# ARM_EURO_Platine1.net
KiCad netlist of a schematic drawn in Altium Designer
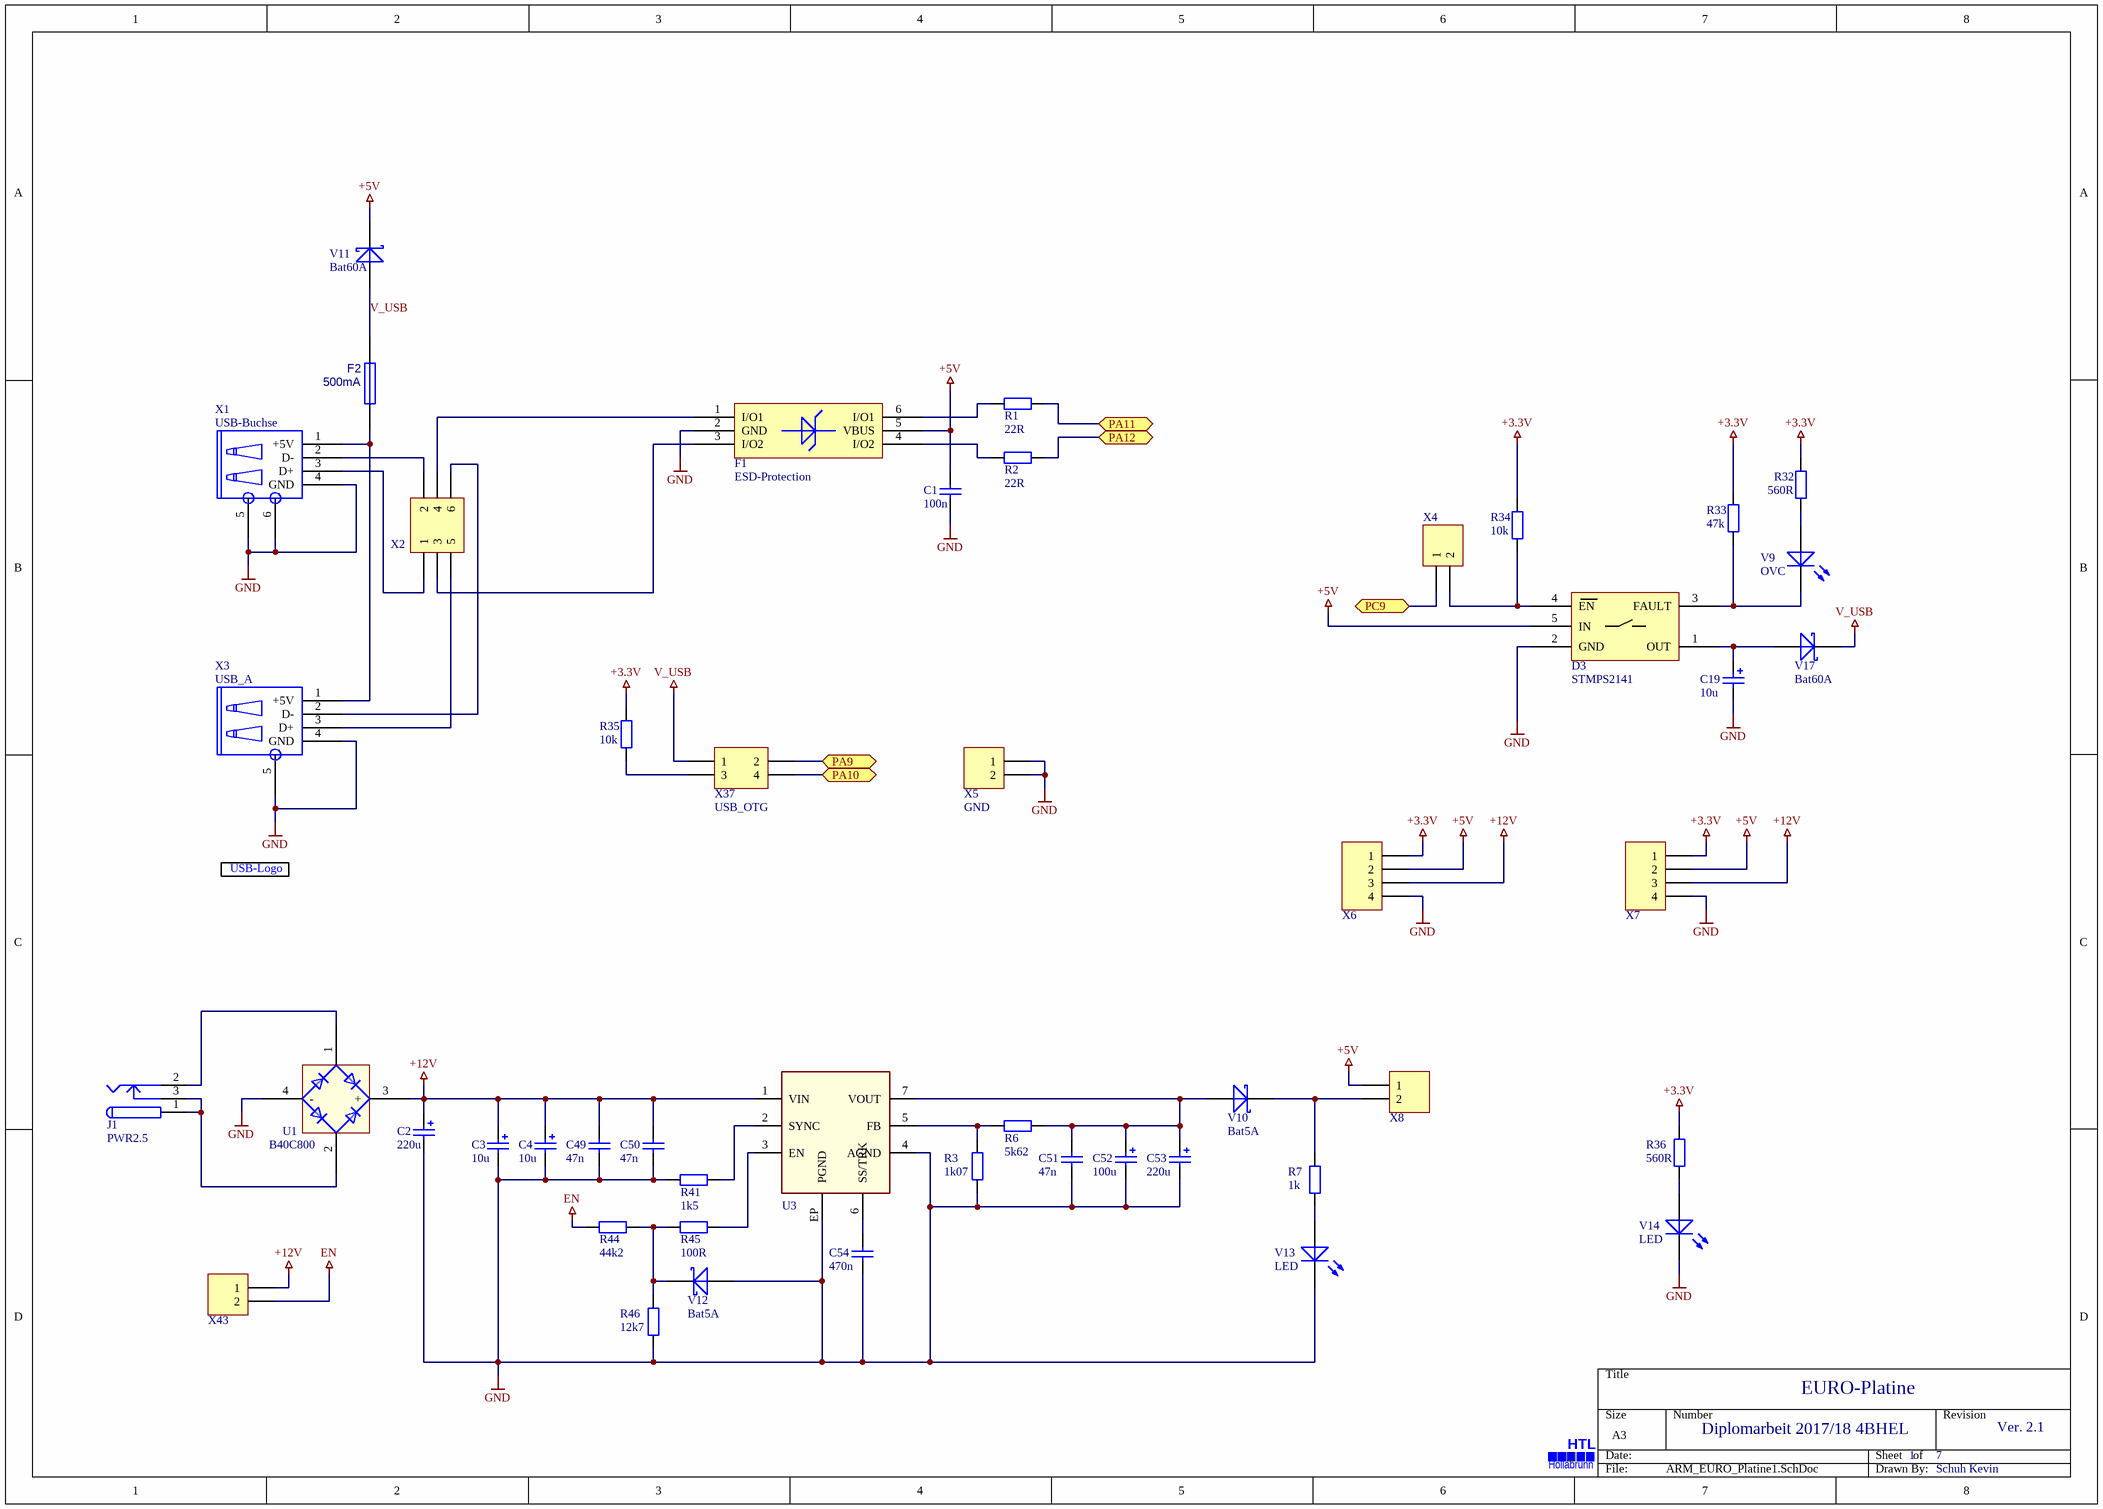
[diagram p0: ARM_EURO_Platine1.SchDoc]

(export (version "E")
  (design (tool "Eeschema 10.0.6"))
  (components
    (comp (ref "*1")
      (value "USB_Logo")
      (footprint "USB_Logo")
      (description "Logo")
      (libsource (lib "ARM_Libary_EURO") (part "USB_Logo"))
    )
    (comp (ref "A1")
      (value "HTL Hollabrunn")
      (footprint "HTL_Logo")
      (libsource (lib "ARM_Libary_EURO") (part "HTL_Logo"))
    )
    (comp (ref "C1")
      (value "100n")
      (footprint "0805_CAP")
      (description "Capacitor_SMD")
      (fields (field (name "Comment") "Cap_Keramik_SMD") (field (name "PUBLISHER") "Altium Limited"))
      (libsource (lib "ARM_Libary_EURO") (part "Cap_Keramik_SMD"))
    )
    (comp (ref "C2")
      (value "220u")
      (footprint "100µF_16V_Kondensator")
      (description "Polarized Capacitor SMD")
      (fields (field (name "Comment") "Cap_Pol_SMD") (field (name "PUBLISHER") "Altium Limited"))
      (libsource (lib "ARM_Libary_EURO") (part "Cap_Pol_SMD"))
    )
    (comp (ref "C3")
      (value "10u")
      (footprint "1411_Cap_Pol_Tantal")
      (description "Polarized Capacitor")
      (fields (field (name "Comment") "Cap_Pol_Tantal") (field (name "PUBLISHER") "Altium Limited"))
      (libsource (lib "ARM_Libary_EURO") (part "Cap_Pol_Tantal"))
    )
    (comp (ref "C4")
      (value "10u")
      (footprint "1411_Cap_Pol_Tantal")
      (description "Polarized Capacitor")
      (fields (field (name "Comment") "Cap_Pol_Tantal") (field (name "PUBLISHER") "Altium Limited"))
      (libsource (lib "ARM_Libary_EURO") (part "Cap_Pol_Tantal"))
    )
    (comp (ref "C19")
      (value "10u")
      (footprint "100µF_16V_Kondensator")
      (description "Polarized Capacitor SMD")
      (fields (field (name "Comment") "Cap_Pol_SMD") (field (name "PUBLISHER") "Altium Limited"))
      (libsource (lib "ARM_Libary_EURO") (part "Cap_Pol_SMD"))
    )
    (comp (ref "C49")
      (value "47n")
      (footprint "0805_CAP")
      (description "Capacitor_SMD")
      (fields (field (name "Comment") "Cap_Keramik_SMD") (field (name "PUBLISHER") "Altium Limited"))
      (libsource (lib "ARM_Libary_EURO") (part "Cap_Keramik_SMD"))
    )
    (comp (ref "C50")
      (value "47n")
      (footprint "0805_CAP")
      (description "Capacitor_SMD")
      (fields (field (name "Comment") "Cap_Keramik_SMD") (field (name "PUBLISHER") "Altium Limited"))
      (libsource (lib "ARM_Libary_EURO") (part "Cap_Keramik_SMD"))
    )
    (comp (ref "C51")
      (value "47n")
      (footprint "0805_CAP")
      (description "Capacitor_SMD")
      (fields (field (name "Comment") "Cap_Keramik_SMD") (field (name "PUBLISHER") "Altium Limited"))
      (libsource (lib "ARM_Libary_EURO") (part "Cap_Keramik_SMD"))
    )
    (comp (ref "C52")
      (value "100u")
      (footprint "100µF_16V_Kondensator")
      (description "Polarized Capacitor SMD")
      (fields (field (name "Comment") "Cap_Pol_SMD") (field (name "PUBLISHER") "Altium Limited"))
      (libsource (lib "ARM_Libary_EURO") (part "Cap_Pol_SMD"))
    )
    (comp (ref "C53")
      (value "220u")
      (footprint "100µF_16V_Kondensator")
      (description "Polarized Capacitor SMD")
      (fields (field (name "Comment") "Cap_Pol_SMD") (field (name "PUBLISHER") "Altium Limited"))
      (libsource (lib "ARM_Libary_EURO") (part "Cap_Pol_SMD"))
    )
    (comp (ref "C54")
      (value "470n")
      (footprint "0805_CAP")
      (description "Capacitor_SMD")
      (fields (field (name "Comment") "Cap_Keramik_SMD") (field (name "PUBLISHER") "Altium Limited"))
      (libsource (lib "ARM_Libary_EURO") (part "Cap_Keramik_SMD"))
    )
    (comp (ref "D3")
      (value "STMPS2141")
      (footprint "STMPS2141")
      (description "Power Switch")
      (libsource (lib "ARM_Libary_EURO") (part "STMPS2141"))
    )
    (comp (ref "F1")
      (value "ESD-Protection")
      (footprint "USBLC6_2")
      (description "Schutz vor entladungen über USB-Buchse")
      (libsource (lib "ARM_Libary_EURO") (part "USBLC6_2"))
    )
    (comp (ref "F2")
      (value "500mA")
      (footprint "Polyfuse")
      (description "Fuse")
      (fields (field (name "PUBLISHER") "Altium Limited"))
      (libsource (lib "ARM_Libary_EURO") (part "Fuse"))
    )
    (comp (ref "J1")
      (value "PWR2.5")
      (footprint "PowerJack")
      (description "Low Voltage Power Supply Connector")
      (fields (field (name "PUBLISHER") "Altium Limited"))
      (libsource (lib "ARM_Libary_EURO") (part "PWR2.5"))
    )
    (comp (ref "R1")
      (value "22R")
      (footprint "0805_Res")
      (description "Resistor")
      (fields (field (name "Comment") "Res_SMD") (field (name "PUBLISHER") "Altium Limited"))
      (libsource (lib "") (part "Res_SMD_2"))
    )
    (comp (ref "R2")
      (value "22R")
      (footprint "0805_Res")
      (description "Resistor")
      (fields (field (name "Comment") "Res_SMD") (field (name "PUBLISHER") "Altium Limited"))
      (libsource (lib "") (part "Res_SMD_2"))
    )
    (comp (ref "R3")
      (value "1k07")
      (footprint "0805_Res")
      (description "Resistor")
      (fields (field (name "Comment") "Res_SMD") (field (name "PUBLISHER") "Altium Limited"))
      (libsource (lib "") (part "Res_SMD_1"))
    )
    (comp (ref "R6")
      (value "5k62")
      (footprint "0805_Res")
      (description "Resistor")
      (fields (field (name "Comment") "Res_SMD") (field (name "PUBLISHER") "Altium Limited"))
      (libsource (lib "ARM_Libary_EURO") (part "Res_SMD"))
    )
    (comp (ref "R7")
      (value "1k")
      (footprint "0805_Res")
      (description "Resistor")
      (fields (field (name "Comment") "Res_SMD") (field (name "PUBLISHER") "Altium Limited"))
      (libsource (lib "") (part "Res_SMD_1"))
    )
    (comp (ref "R32")
      (value "560R")
      (footprint "0805_Res")
      (description "Resistor")
      (fields (field (name "Comment") "Res_SMD") (field (name "PUBLISHER") "Altium Limited"))
      (libsource (lib "") (part "Res_SMD_1"))
    )
    (comp (ref "R33")
      (value "47k")
      (footprint "0805_Res")
      (description "Resistor")
      (fields (field (name "Comment") "Res_SMD") (field (name "PUBLISHER") "Altium Limited"))
      (libsource (lib "") (part "Res_SMD_1"))
    )
    (comp (ref "R34")
      (value "10k")
      (footprint "0805_Res")
      (description "Resistor")
      (fields (field (name "Comment") "Res_SMD") (field (name "PUBLISHER") "Altium Limited"))
      (libsource (lib "") (part "Res_SMD_1"))
    )
    (comp (ref "R35")
      (value "10k")
      (footprint "0805_Res")
      (description "Resistor")
      (fields (field (name "Comment") "Res_SMD") (field (name "PUBLISHER") "Altium Limited"))
      (libsource (lib "") (part "Res_SMD_1"))
    )
    (comp (ref "R36")
      (value "560R")
      (footprint "0805_Res")
      (description "Resistor")
      (fields (field (name "Comment") "Res_SMD") (field (name "PUBLISHER") "Altium Limited"))
      (libsource (lib "") (part "Res_SMD_1"))
    )
    (comp (ref "R41")
      (value "1k5")
      (footprint "0805_Res")
      (description "Resistor")
      (fields (field (name "Comment") "Res_SMD") (field (name "PUBLISHER") "Altium Limited"))
      (libsource (lib "ARM_Libary_EURO") (part "Res_SMD"))
    )
    (comp (ref "R44")
      (value "44k2")
      (footprint "0805_Res")
      (description "Resistor")
      (fields (field (name "Comment") "Res_SMD") (field (name "PUBLISHER") "Altium Limited"))
      (libsource (lib "ARM_Libary_EURO") (part "Res_SMD"))
    )
    (comp (ref "R45")
      (value "100R")
      (footprint "0805_Res")
      (description "Resistor")
      (fields (field (name "Comment") "Res_SMD") (field (name "PUBLISHER") "Altium Limited"))
      (libsource (lib "ARM_Libary_EURO") (part "Res_SMD"))
    )
    (comp (ref "R46")
      (value "12k7")
      (footprint "0805_Res")
      (description "Resistor")
      (fields (field (name "Comment") "Res_SMD") (field (name "PUBLISHER") "Altium Limited"))
      (libsource (lib "") (part "Res_SMD_1"))
    )
    (comp (ref "U1")
      (value "B40C800")
      (footprint "Diodengleichrichter")
      (description "Brueckengleichrichter")
      (libsource (lib "ARM_Libary_EURO") (part "Brueckengleichrichter"))
    )
    (comp (ref "U3")
      (value "171050601")
      (footprint "TO263-7EP")
      (description "VDRM Variable Step Down Regulator Module, TO263-7EP")
      (fields (field (name "PUBLISHER") "Wurth Elektronik"))
      (libsource (lib "ARM_Libary_EURO") (part "171050601"))
    )
    (comp (ref "V9")
      (value "OVC")
      (footprint "0805_LED")
      (description "Typical RED, GREEN, YELLOW, AMBER GaAs LED")
      (fields (field (name "PUBLISHER") "Altium Limited"))
      (libsource (lib "ARM_Libary_EURO") (part "LED_SMD"))
    )
    (comp (ref "V10")
      (value "Bat5A")
      (footprint "BAT254_Schottky")
      (description "Diode")
      (libsource (lib "ARM_Libary_EURO") (part "Bat60A"))
    )
    (comp (ref "V11")
      (value "Bat60A")
      (footprint "BAT254_Schottky")
      (description "Diode")
      (libsource (lib "ARM_Libary_EURO") (part "Bat60A"))
    )
    (comp (ref "V12")
      (value "Bat5A")
      (footprint "BAT254_Schottky")
      (description "Diode")
      (libsource (lib "ARM_Libary_EURO") (part "Bat60A"))
    )
    (comp (ref "V13")
      (value "LED")
      (footprint "0805_LED")
      (description "Typical RED, GREEN, YELLOW, AMBER GaAs LED")
      (fields (field (name "PUBLISHER") "Altium Limited"))
      (libsource (lib "ARM_Libary_EURO") (part "LED_SMD"))
    )
    (comp (ref "V14")
      (value "LED")
      (footprint "0805_LED")
      (description "Typical RED, GREEN, YELLOW, AMBER GaAs LED")
      (fields (field (name "PUBLISHER") "Altium Limited"))
      (libsource (lib "ARM_Libary_EURO") (part "LED_SMD"))
    )
    (comp (ref "V17")
      (value "Bat60A")
      (footprint "BAT254_Schottky")
      (description "Diode")
      (libsource (lib "ARM_Libary_EURO") (part "Bat60A"))
    )
    (comp (ref "X1")
      (value "USB-Buchse")
      (footprint "USB_B")
      (description "USB Buchse (B)")
      (libsource (lib "ARM_Libary_EURO") (part "USB_Buchse_B"))
    )
    (comp (ref "X2")
      (value "Header_3x2")
      (footprint "HDR2X3")
      (description "Header, 3x2-Pin")
      (fields (field (name "PUBLISHER") "Altium Limited"))
      (libsource (lib "ARM_Libary_EURO") (part "Header_3x2"))
    )
    (comp (ref "X3")
      (value "USB_A")
      (footprint "USB_A")
      (description "USB Buchse (A)")
      (libsource (lib "ARM_Libary_EURO") (part "USB_Buchse_A"))
    )
    (comp (ref "X4")
      (value "Header")
      (footprint "HDR1X2")
      (description "Header, 2-Pin")
      (fields (field (name "PUBLISHER") "Altium Limited"))
      (libsource (lib "ARM_Libary_EURO") (part "Header_2"))
    )
    (comp (ref "X5")
      (value "GND")
      (footprint "HDR1X2")
      (description "Header, 2-Pin")
      (fields (field (name "PUBLISHER") "Altium Limited"))
      (libsource (lib "ARM_Libary_EURO") (part "Masseschleife"))
    )
    (comp (ref "X6")
      (value "Header_4")
      (footprint "HDR1X4")
      (description "Header, 3-Pin")
      (fields (field (name "PUBLISHER") "Altium Limited"))
      (libsource (lib "ARM_Libary_EURO") (part "Header_4"))
    )
    (comp (ref "X7")
      (value "Header_4")
      (footprint "HDR1X4")
      (description "Header, 3-Pin")
      (fields (field (name "PUBLISHER") "Altium Limited"))
      (libsource (lib "ARM_Libary_EURO") (part "Header_4"))
    )
    (comp (ref "X8")
      (value "Header")
      (footprint "HDR1X2")
      (description "Header, 2-Pin")
      (fields (field (name "PUBLISHER") "Altium Limited"))
      (libsource (lib "") (part "Header_2_2"))
    )
    (comp (ref "X37")
      (value "USB_OTG")
      (footprint "HDR2X2")
      (description "Header, 3x2-Pin")
      (fields (field (name "PUBLISHER") "Altium Limited"))
      (libsource (lib "ARM_Libary_EURO") (part "Header_2x2"))
    )
    (comp (ref "X43")
      (value "Header")
      (footprint "HDR1X2")
      (description "Header, 2-Pin")
      (fields (field (name "PUBLISHER") "Altium Limited"))
      (libsource (lib "") (part "Header_2_1"))
    )
  )
  (nets
    (net (code "1") (name "+3.3V") (class "Default")
      (node (ref "R32") (pin "2") (pinfunction "2_2") (pintype "passive"))
      (node (ref "R33") (pin "2") (pinfunction "2_2") (pintype "passive"))
      (node (ref "R34") (pin "2") (pinfunction "2_2") (pintype "passive"))
      (node (ref "R35") (pin "2") (pinfunction "2_2") (pintype "passive"))
      (node (ref "R36") (pin "2") (pinfunction "2_2") (pintype "passive"))
      (node (ref "X6") (pin "1") (pinfunction "1_1") (pintype "passive"))
      (node (ref "X7") (pin "1") (pinfunction "1_1") (pintype "passive"))
    )
    (net (code "2") (name "+5V") (class "Default")
      (node (ref "C1") (pin "2") (pinfunction "2_2") (pintype "passive"))
      (node (ref "D3") (pin "5") (pinfunction "IN_5") (pintype "passive"))
      (node (ref "F1") (pin "5") (pinfunction "VBUS_5") (pintype "passive"))
      (node (ref "V11") (pin "1") (pinfunction "1_1") (pintype "passive"))
      (node (ref "X6") (pin "2") (pinfunction "2_2") (pintype "passive"))
      (node (ref "X7") (pin "2") (pinfunction "2_2") (pintype "passive"))
      (node (ref "X8") (pin "1") (pinfunction "1_1") (pintype "passive"))
    )
    (net (code "3") (name "+12V") (class "Default")
      (node (ref "C2") (pin "1") (pinfunction "1_1") (pintype "passive"))
      (node (ref "C3") (pin "1") (pinfunction "1_1") (pintype "passive"))
      (node (ref "C4") (pin "1") (pinfunction "1_1") (pintype "passive"))
      (node (ref "C49") (pin "2") (pinfunction "2_2") (pintype "passive"))
      (node (ref "C50") (pin "1") (pinfunction "1_1") (pintype "passive"))
      (node (ref "U1") (pin "3") (pinfunction "+_3") (pintype "passive"))
      (node (ref "U3") (pin "1") (pinfunction "VIN_1") (pintype "passive"))
      (node (ref "X43") (pin "1") (pinfunction "1_1") (pintype "passive"))
      (node (ref "X6") (pin "3") (pinfunction "3_3") (pintype "passive"))
      (node (ref "X7") (pin "3") (pinfunction "3_3") (pintype "passive"))
    )
    (net (code "4") (name "/PA9") (class "Default")
      (node (ref "X37") (pin "2") (pinfunction "2_2") (pintype "passive"))
    )
    (net (code "5") (name "/PA10") (class "Default")
      (node (ref "X37") (pin "4") (pinfunction "4_4") (pintype "passive"))
    )
    (net (code "6") (name "/PA11") (class "Default")
      (node (ref "R1") (pin "2") (pinfunction "2_2") (pintype "passive"))
    )
    (net (code "7") (name "/PA12") (class "Default")
      (node (ref "R2") (pin "2") (pinfunction "2_2") (pintype "passive"))
    )
    (net (code "8") (name "/PC9") (class "Default")
      (node (ref "X4") (pin "1") (pinfunction "1_1") (pintype "passive"))
    )
    (net (code "9") (name "EN") (class "Default")
      (node (ref "R44") (pin "2") (pinfunction "2_2") (pintype "passive"))
      (node (ref "X43") (pin "2") (pinfunction "2_2") (pintype "passive"))
    )
    (net (code "10") (name "GND") (class "Default")
      (node (ref "C1") (pin "1") (pinfunction "1_1") (pintype "passive"))
      (node (ref "C19") (pin "2") (pinfunction "2_2") (pintype "passive"))
      (node (ref "C2") (pin "2") (pinfunction "2_2") (pintype "passive"))
      (node (ref "C3") (pin "2") (pinfunction "2_2") (pintype "passive"))
      (node (ref "C4") (pin "2") (pinfunction "2_2") (pintype "passive"))
      (node (ref "C49") (pin "1") (pinfunction "1_1") (pintype "passive"))
      (node (ref "C50") (pin "2") (pinfunction "2_2") (pintype "passive"))
      (node (ref "C51") (pin "2") (pinfunction "2_2") (pintype "passive"))
      (node (ref "C52") (pin "2") (pinfunction "2_2") (pintype "passive"))
      (node (ref "C53") (pin "2") (pinfunction "2_2") (pintype "passive"))
      (node (ref "C54") (pin "2") (pinfunction "2_2") (pintype "passive"))
      (node (ref "D3") (pin "2") (pinfunction "GND_2") (pintype "passive"))
      (node (ref "F1") (pin "2") (pinfunction "GND_2") (pintype "passive"))
      (node (ref "R3") (pin "1") (pinfunction "1_1") (pintype "passive"))
      (node (ref "R41") (pin "2") (pinfunction "2_2") (pintype "passive"))
      (node (ref "R46") (pin "1") (pinfunction "1_1") (pintype "passive"))
      (node (ref "U1") (pin "4") (pinfunction "-_4") (pintype "passive"))
      (node (ref "U3") (pin "4") (pinfunction "AGND_4") (pintype "passive"))
      (node (ref "U3") (pin "EP") (pinfunction "PGND_EP") (pintype "passive"))
      (node (ref "V12") (pin "2") (pinfunction "2_2") (pintype "passive"))
      (node (ref "V13") (pin "2") (pinfunction "K_2") (pintype "passive"))
      (node (ref "V14") (pin "2") (pinfunction "K_2") (pintype "passive"))
      (node (ref "X1") (pin "4") (pinfunction "GND_4") (pintype "passive"))
      (node (ref "X1") (pin "5") (pinfunction "GND_5") (pintype "passive"))
      (node (ref "X1") (pin "6") (pinfunction "GND_6") (pintype "passive"))
      (node (ref "X3") (pin "4") (pinfunction "GND_4") (pintype "passive"))
      (node (ref "X3") (pin "5") (pinfunction "GND_5") (pintype "passive"))
      (node (ref "X5") (pin "1") (pinfunction "1_1") (pintype "passive"))
      (node (ref "X5") (pin "2") (pinfunction "2_2") (pintype "passive"))
      (node (ref "X6") (pin "4") (pinfunction "4_4") (pintype "passive"))
      (node (ref "X7") (pin "4") (pinfunction "4_4") (pintype "passive"))
    )
    (net (code "11") (name "Net-(D3-EN)") (class "Default")
      (node (ref "D3") (pin "4") (pinfunction "EN_4") (pintype "passive"))
      (node (ref "R34") (pin "1") (pinfunction "1_1") (pintype "passive"))
      (node (ref "X4") (pin "2") (pinfunction "2_2") (pintype "passive"))
    )
    (net (code "12") (name "Net-(D3-FAULT)") (class "Default")
      (node (ref "D3") (pin "3") (pinfunction "FAULT_3") (pintype "passive"))
      (node (ref "R33") (pin "1") (pinfunction "1_1") (pintype "passive"))
      (node (ref "V9") (pin "2") (pinfunction "K_2") (pintype "passive"))
    )
    (net (code "13") (name "Net-(D3-OUT)") (class "Default")
      (node (ref "C19") (pin "1") (pinfunction "1_1") (pintype "passive"))
      (node (ref "D3") (pin "1") (pinfunction "OUT_1") (pintype "passive"))
      (node (ref "V17") (pin "2") (pinfunction "2_2") (pintype "passive"))
    )
    (net (code "14") (name "Net-(F1-I{slash}O1-Pad1)") (class "Default")
      (node (ref "F1") (pin "1") (pinfunction "I/O1_1") (pintype "passive"))
      (node (ref "X2") (pin "4") (pinfunction "4_4") (pintype "passive"))
    )
    (net (code "15") (name "Net-(F1-I{slash}O1-Pad6)") (class "Default")
      (node (ref "F1") (pin "6") (pinfunction "I/O1_6") (pintype "passive"))
      (node (ref "R1") (pin "1") (pinfunction "1_1") (pintype "passive"))
    )
    (net (code "16") (name "Net-(F1-I{slash}O2-Pad3)") (class "Default")
      (node (ref "F1") (pin "3") (pinfunction "I/O2_3") (pintype "passive"))
      (node (ref "X2") (pin "3") (pinfunction "3_3") (pintype "passive"))
    )
    (net (code "17") (name "Net-(F1-I{slash}O2-Pad4)") (class "Default")
      (node (ref "F1") (pin "4") (pinfunction "I/O2_4") (pintype "passive"))
      (node (ref "R2") (pin "1") (pinfunction "1_1") (pintype "passive"))
    )
    (net (code "18") (name "Net-(J1-Pad1)") (class "Default")
      (node (ref "J1") (pin "1") (pinfunction "1_1") (pintype "power_in"))
      (node (ref "J1") (pin "3") (pinfunction "3_3") (pintype "power_in"))
      (node (ref "U1") (pin "2") (pinfunction "2_2") (pintype "passive"))
    )
    (net (code "19") (name "Net-(J1-Pad2)") (class "Default")
      (node (ref "J1") (pin "2") (pinfunction "2_2") (pintype "power_in"))
      (node (ref "U1") (pin "1") (pinfunction "1_1") (pintype "passive"))
    )
    (net (code "20") (name "Net-(R7-Pad2)") (class "Default")
      (node (ref "R7") (pin "2") (pinfunction "2_2") (pintype "passive"))
      (node (ref "V10") (pin "1") (pinfunction "1_1") (pintype "passive"))
      (node (ref "X8") (pin "2") (pinfunction "2_2") (pintype "passive"))
    )
    (net (code "21") (name "Net-(R35-Pad1)") (class "Default")
      (node (ref "R35") (pin "1") (pinfunction "1_1") (pintype "passive"))
      (node (ref "X37") (pin "3") (pinfunction "3_3") (pintype "passive"))
    )
    (net (code "22") (name "Net-(R44-Pad1)") (class "Default")
      (node (ref "R44") (pin "1") (pinfunction "1_1") (pintype "passive"))
      (node (ref "R45") (pin "2") (pinfunction "2_2") (pintype "passive"))
      (node (ref "R46") (pin "2") (pinfunction "2_2") (pintype "passive"))
      (node (ref "V12") (pin "1") (pinfunction "1_1") (pintype "passive"))
    )
    (net (code "23") (name "Net-(U3-EN)") (class "Default")
      (node (ref "R45") (pin "1") (pinfunction "1_1") (pintype "passive"))
      (node (ref "U3") (pin "3") (pinfunction "EN_3") (pintype "passive"))
    )
    (net (code "24") (name "Net-(U3-FB)") (class "Default")
      (node (ref "R3") (pin "2") (pinfunction "2_2") (pintype "passive"))
      (node (ref "R6") (pin "2") (pinfunction "2_2") (pintype "passive"))
      (node (ref "U3") (pin "5") (pinfunction "FB_5") (pintype "passive"))
    )
    (net (code "25") (name "Net-(U3-SS{slash}TRK)") (class "Default")
      (node (ref "C54") (pin "1") (pinfunction "1_1") (pintype "passive"))
      (node (ref "U3") (pin "6") (pinfunction "SS/TRK_6") (pintype "passive"))
    )
    (net (code "26") (name "Net-(U3-SYNC)") (class "Default")
      (node (ref "R41") (pin "1") (pinfunction "1_1") (pintype "passive"))
      (node (ref "U3") (pin "2") (pinfunction "SYNC_2") (pintype "passive"))
    )
    (net (code "27") (name "Net-(U3-VOUT)") (class "Default")
      (node (ref "C51") (pin "1") (pinfunction "1_1") (pintype "passive"))
      (node (ref "C52") (pin "1") (pinfunction "1_1") (pintype "passive"))
      (node (ref "C53") (pin "1") (pinfunction "1_1") (pintype "passive"))
      (node (ref "R6") (pin "1") (pinfunction "1_1") (pintype "passive"))
      (node (ref "U3") (pin "7") (pinfunction "VOUT_7") (pintype "passive"))
      (node (ref "V10") (pin "2") (pinfunction "2_2") (pintype "passive"))
    )
    (net (code "28") (name "Net-(V9-A)") (class "Default")
      (node (ref "R32") (pin "1") (pinfunction "1_1") (pintype "passive"))
      (node (ref "V9") (pin "1") (pinfunction "A_1") (pintype "passive"))
    )
    (net (code "29") (name "Net-(V13-A)") (class "Default")
      (node (ref "R7") (pin "1") (pinfunction "1_1") (pintype "passive"))
      (node (ref "V13") (pin "1") (pinfunction "A_1") (pintype "passive"))
    )
    (net (code "30") (name "Net-(V14-A)") (class "Default")
      (node (ref "R36") (pin "1") (pinfunction "1_1") (pintype "passive"))
      (node (ref "V14") (pin "1") (pinfunction "A_1") (pintype "passive"))
    )
    (net (code "31") (name "Net-(X1-+5V)") (class "Default")
      (node (ref "F2") (pin "1") (pinfunction "1_1") (pintype "passive"))
      (node (ref "X1") (pin "1") (pinfunction "+5V_1") (pintype "passive"))
      (node (ref "X3") (pin "1") (pinfunction "+5V_1") (pintype "passive"))
    )
    (net (code "32") (name "Net-(X1-D+)") (class "Default")
      (node (ref "X1") (pin "3") (pinfunction "D+_3") (pintype "passive"))
      (node (ref "X2") (pin "1") (pinfunction "1_1") (pintype "passive"))
    )
    (net (code "33") (name "Net-(X1-D-)") (class "Default")
      (node (ref "X1") (pin "2") (pinfunction "D-_2") (pintype "passive"))
      (node (ref "X2") (pin "2") (pinfunction "2_2") (pintype "passive"))
    )
    (net (code "34") (name "Net-(X3-D+)") (class "Default")
      (node (ref "X2") (pin "5") (pinfunction "5_5") (pintype "passive"))
      (node (ref "X3") (pin "3") (pinfunction "D+_3") (pintype "passive"))
    )
    (net (code "35") (name "Net-(X3-D-)") (class "Default")
      (node (ref "X2") (pin "6") (pinfunction "6_6") (pintype "passive"))
      (node (ref "X3") (pin "2") (pinfunction "D-_2") (pintype "passive"))
    )
    (net (code "36") (name "V_USB") (class "Default")
      (node (ref "F2") (pin "2") (pinfunction "2_2") (pintype "passive"))
      (node (ref "V11") (pin "2") (pinfunction "2_2") (pintype "passive"))
      (node (ref "V17") (pin "1") (pinfunction "1_1") (pintype "passive"))
      (node (ref "X37") (pin "1") (pinfunction "1_1") (pintype "passive"))
    )
  )
)
